# Falcon.net
KiCad netlist of a schematic drawn in Altium Designer
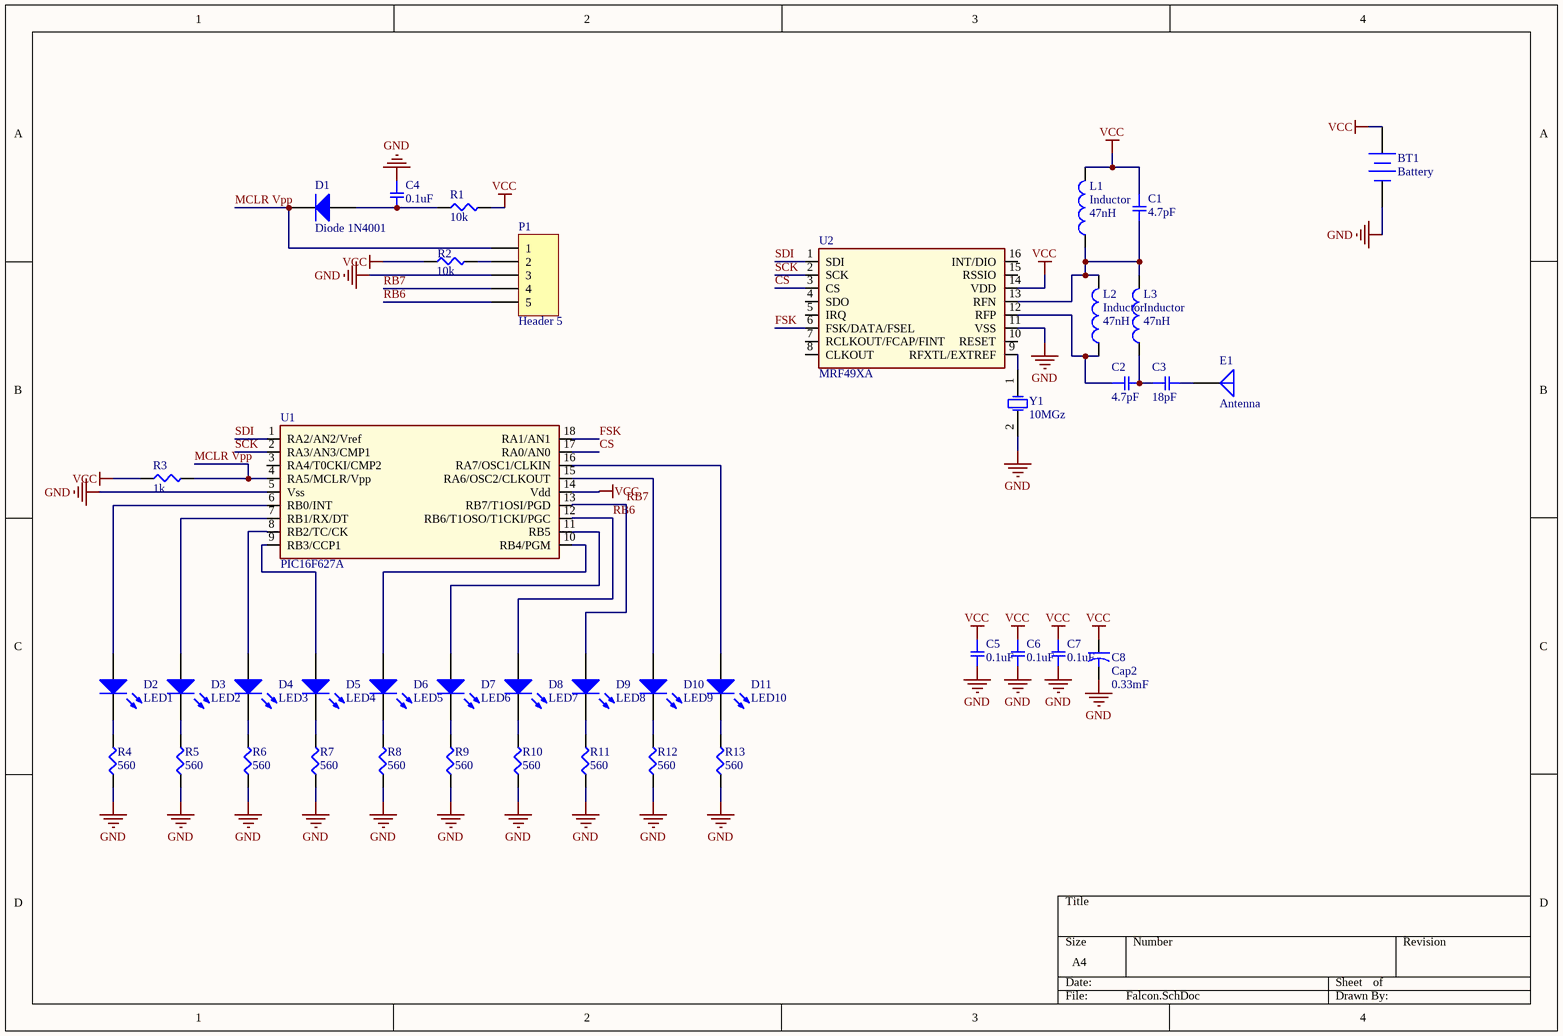
[diagram p0: Falcon.SchDoc]

(export (version "E")
  (design (tool "Eeschema 10.0.6"))
  (components
    (comp (ref "BT1")
      (value "Battery")
      (footprint "BAT-2")
      (description "Multicell Battery")
      (fields (field (name "PUBLISHER") "Altium Limited"))
      (libsource (lib "Miscellaneous Devices") (part "Battery"))
    )
    (comp (ref "C1")
      (value "4.7pF")
      (footprint "SMD-1206C")
      (description "CAP CER 0.033UF 250V X7T 1206")
      (fields
        (field (name "DIGI-KEY PART NUMBER") "490-13989-1-ND")
        (field (name "PART NUMBER") "GC331AD72E333KX01D")
      )
      (libsource (lib "capacitor_murata_1206") (part "GC331AD72E333KX01D"))
    )
    (comp (ref "C2")
      (value "4.7pF")
      (footprint "SMD-1206C")
      (description "CAP CER 0.033UF 250V X7T 1206")
      (fields
        (field (name "DIGI-KEY PART NUMBER") "490-13989-1-ND")
        (field (name "PART NUMBER") "GC331AD72E333KX01D")
      )
      (libsource (lib "capacitor_murata_1206") (part "GC331AD72E333KX01D"))
    )
    (comp (ref "C3")
      (value "18pF")
      (footprint "SMD-1206C")
      (description "CAP CER 0.033UF 250V X7T 1206")
      (fields
        (field (name "DIGI-KEY PART NUMBER") "490-13989-1-ND")
        (field (name "PART NUMBER") "GC331AD72E333KX01D")
      )
      (libsource (lib "capacitor_murata_1206") (part "GC331AD72E333KX01D"))
    )
    (comp (ref "C4")
      (value "0.1uF")
      (footprint "SMD-0805C")
      (description "CAP CER 10000PF 250V X7T 0805")
      (fields
        (field (name "DIGI-KEY PART NUMBER") "490-13986-1-ND")
        (field (name "PART NUMBER") "GC321AD72E103KX01D")
      )
      (libsource (lib "capacitor_murata_0805") (part "GC321AD72E103KX01D"))
    )
    (comp (ref "C5")
      (value "0.1uF")
      (footprint "SMD-0805C")
      (description "CAP CER 10000PF 250V X7T 0805")
      (fields
        (field (name "DIGI-KEY PART NUMBER") "490-13986-1-ND")
        (field (name "PART NUMBER") "GC321AD72E103KX01D")
      )
      (libsource (lib "capacitor_murata_0805") (part "GC321AD72E103KX01D"))
    )
    (comp (ref "C6")
      (value "0.1uF")
      (footprint "SMD-0805C")
      (description "CAP CER 10000PF 250V X7T 0805")
      (fields
        (field (name "DIGI-KEY PART NUMBER") "490-13986-1-ND")
        (field (name "PART NUMBER") "GC321AD72E103KX01D")
      )
      (libsource (lib "capacitor_murata_0805") (part "GC321AD72E103KX01D"))
    )
    (comp (ref "C7")
      (value "0.1uF")
      (footprint "SMD-0805C")
      (description "CAP CER 10000PF 250V X7T 0805")
      (fields
        (field (name "DIGI-KEY PART NUMBER") "490-13986-1-ND")
        (field (name "PART NUMBER") "GC321AD72E103KX01D")
      )
      (libsource (lib "capacitor_murata_0805") (part "GC321AD72E103KX01D"))
    )
    (comp (ref "C8")
      (value "Cap2")
      (footprint "CAPR5-4X5")
      (description "Capacitor")
      (fields (field (name "ALTIUM_VALUE") "0.33mF") (field (name "PUBLISHER") "Altium Limited"))
      (libsource (lib "Miscellaneous Devices") (part "Cap2"))
    )
    (comp (ref "D1")
      (value "Diode 1N4001")
      (footprint "DO-41")
      (description "1 Amp General Purpose Rectifier")
      (fields (field (name "PUBLISHER") "Altium Limited"))
      (libsource (lib "Miscellaneous Devices") (part "Diode 1N4001"))
    )
    (comp (ref "D2")
      (value "LED1")
      (footprint "3.5X2.8X1.9")
      (description "Typical BLUE SiC LED")
      (fields (field (name "PUBLISHER") "Altium Limited"))
      (libsource (lib "Miscellaneous Devices") (part "LED3"))
    )
    (comp (ref "D3")
      (value "LED2")
      (footprint "3.5X2.8X1.9")
      (description "Typical BLUE SiC LED")
      (fields (field (name "PUBLISHER") "Altium Limited"))
      (libsource (lib "Miscellaneous Devices") (part "LED3"))
    )
    (comp (ref "D4")
      (value "LED3")
      (footprint "3.5X2.8X1.9")
      (description "Typical BLUE SiC LED")
      (fields (field (name "PUBLISHER") "Altium Limited"))
      (libsource (lib "Miscellaneous Devices") (part "LED3"))
    )
    (comp (ref "D5")
      (value "LED4")
      (footprint "3.5X2.8X1.9")
      (description "Typical BLUE SiC LED")
      (fields (field (name "PUBLISHER") "Altium Limited"))
      (libsource (lib "Miscellaneous Devices") (part "LED3"))
    )
    (comp (ref "D6")
      (value "LED5")
      (footprint "3.5X2.8X1.9")
      (description "Typical BLUE SiC LED")
      (fields (field (name "PUBLISHER") "Altium Limited"))
      (libsource (lib "Miscellaneous Devices") (part "LED3"))
    )
    (comp (ref "D7")
      (value "LED6")
      (footprint "3.5X2.8X1.9")
      (description "Typical BLUE SiC LED")
      (fields (field (name "PUBLISHER") "Altium Limited"))
      (libsource (lib "Miscellaneous Devices") (part "LED3"))
    )
    (comp (ref "D8")
      (value "LED7")
      (footprint "3.5X2.8X1.9")
      (description "Typical BLUE SiC LED")
      (fields (field (name "PUBLISHER") "Altium Limited"))
      (libsource (lib "Miscellaneous Devices") (part "LED3"))
    )
    (comp (ref "D9")
      (value "LED8")
      (footprint "3.5X2.8X1.9")
      (description "Typical BLUE SiC LED")
      (fields (field (name "PUBLISHER") "Altium Limited"))
      (libsource (lib "Miscellaneous Devices") (part "LED3"))
    )
    (comp (ref "D10")
      (value "LED9")
      (footprint "3.5X2.8X1.9")
      (description "Typical BLUE SiC LED")
      (fields (field (name "PUBLISHER") "Altium Limited"))
      (libsource (lib "Miscellaneous Devices") (part "LED3"))
    )
    (comp (ref "D11")
      (value "LED10")
      (footprint "3.5X2.8X1.9")
      (description "Typical BLUE SiC LED")
      (fields (field (name "PUBLISHER") "Altium Limited"))
      (libsource (lib "Miscellaneous Devices") (part "LED3"))
    )
    (comp (ref "E1")
      (value "Antenna")
      (footprint "PIN1")
      (description "Generic Antenna")
      (fields (field (name "PUBLISHER") "Altium Limited"))
      (libsource (lib "Miscellaneous Devices") (part "Antenna"))
    )
    (comp (ref "L1")
      (value "Inductor")
      (footprint "0402-A")
      (fields (field (name "ALTIUM_VALUE") "47nH") (field (name "PUBLISHER") "Altium Limited"))
      (libsource (lib "Miscellaneous Devices") (part "Inductor"))
    )
    (comp (ref "L2")
      (value "Inductor")
      (footprint "0402-A")
      (fields (field (name "ALTIUM_VALUE") "47nH") (field (name "PUBLISHER") "Altium Limited"))
      (libsource (lib "Miscellaneous Devices") (part "Inductor"))
    )
    (comp (ref "L3")
      (value "Inductor")
      (footprint "0402-A")
      (fields (field (name "ALTIUM_VALUE") "47nH") (field (name "PUBLISHER") "Altium Limited"))
      (libsource (lib "Miscellaneous Devices") (part "Inductor"))
    )
    (comp (ref "P1")
      (value "Header 5")
      (footprint "HDR1X5")
      (description "Header, 5-Pin")
      (fields (field (name "PUBLISHER") "Altium Limited"))
      (libsource (lib "Miscellaneous Connectors") (part "Header 5"))
    )
    (comp (ref "R1")
      (value "10k")
      (footprint "SMD-0805-RES")
      (description "RES SMD 1 OHM 1% 1/3W 0805")
      (fields (field (name "PART NUMBER") "ERJ-6BQF1R0V") (field (name "DIGI-KEY PART NUMBER") "P17499CT-ND"))
      (libsource (lib "Panasonic_ERJ_0805") (part "ERJ-6BQF1R0V"))
    )
    (comp (ref "R2")
      (value "10k")
      (footprint "SMD-0805-RES")
      (description "RES SMD 1 OHM 1% 1/3W 0805")
      (fields (field (name "PART NUMBER") "ERJ-6BQF1R0V") (field (name "DIGI-KEY PART NUMBER") "P17499CT-ND"))
      (libsource (lib "Panasonic_ERJ_0805") (part "ERJ-6BQF1R0V"))
    )
    (comp (ref "R3")
      (value "1k")
      (footprint "SMD-0805-RES")
      (description "RES SMD 1 OHM 1% 1/3W 0805")
      (fields (field (name "PART NUMBER") "ERJ-6BQF1R0V") (field (name "DIGI-KEY PART NUMBER") "P17499CT-ND"))
      (libsource (lib "Panasonic_ERJ_0805") (part "ERJ-6BQF1R0V"))
    )
    (comp (ref "R4")
      (value "560")
      (footprint "SMD-0805-RES")
      (description "RES SMD 1 OHM 1% 1/3W 0805")
      (fields (field (name "PART NUMBER") "ERJ-6BQF1R0V") (field (name "DIGI-KEY PART NUMBER") "P17499CT-ND"))
      (libsource (lib "Panasonic_ERJ_0805") (part "ERJ-6BQF1R0V"))
    )
    (comp (ref "R5")
      (value "560")
      (footprint "SMD-0805-RES")
      (description "RES SMD 1 OHM 1% 1/3W 0805")
      (fields (field (name "PART NUMBER") "ERJ-6BQF1R0V") (field (name "DIGI-KEY PART NUMBER") "P17499CT-ND"))
      (libsource (lib "Panasonic_ERJ_0805") (part "ERJ-6BQF1R0V"))
    )
    (comp (ref "R6")
      (value "560")
      (footprint "SMD-0805-RES")
      (description "RES SMD 1 OHM 1% 1/3W 0805")
      (fields (field (name "PART NUMBER") "ERJ-6BQF1R0V") (field (name "DIGI-KEY PART NUMBER") "P17499CT-ND"))
      (libsource (lib "Panasonic_ERJ_0805") (part "ERJ-6BQF1R0V"))
    )
    (comp (ref "R7")
      (value "560")
      (footprint "SMD-0805-RES")
      (description "RES SMD 1 OHM 1% 1/3W 0805")
      (fields (field (name "PART NUMBER") "ERJ-6BQF1R0V") (field (name "DIGI-KEY PART NUMBER") "P17499CT-ND"))
      (libsource (lib "Panasonic_ERJ_0805") (part "ERJ-6BQF1R0V"))
    )
    (comp (ref "R8")
      (value "560")
      (footprint "SMD-0805-RES")
      (description "RES SMD 1 OHM 1% 1/3W 0805")
      (fields (field (name "PART NUMBER") "ERJ-6BQF1R0V") (field (name "DIGI-KEY PART NUMBER") "P17499CT-ND"))
      (libsource (lib "Panasonic_ERJ_0805") (part "ERJ-6BQF1R0V"))
    )
    (comp (ref "R9")
      (value "560")
      (footprint "SMD-0805-RES")
      (description "RES SMD 1 OHM 1% 1/3W 0805")
      (fields (field (name "PART NUMBER") "ERJ-6BQF1R0V") (field (name "DIGI-KEY PART NUMBER") "P17499CT-ND"))
      (libsource (lib "Panasonic_ERJ_0805") (part "ERJ-6BQF1R0V"))
    )
    (comp (ref "R10")
      (value "560")
      (footprint "SMD-0805-RES")
      (description "RES SMD 1 OHM 1% 1/3W 0805")
      (fields (field (name "PART NUMBER") "ERJ-6BQF1R0V") (field (name "DIGI-KEY PART NUMBER") "P17499CT-ND"))
      (libsource (lib "Panasonic_ERJ_0805") (part "ERJ-6BQF1R0V"))
    )
    (comp (ref "R11")
      (value "560")
      (footprint "SMD-0805-RES")
      (description "RES SMD 1 OHM 1% 1/3W 0805")
      (fields (field (name "PART NUMBER") "ERJ-6BQF1R0V") (field (name "DIGI-KEY PART NUMBER") "P17499CT-ND"))
      (libsource (lib "Panasonic_ERJ_0805") (part "ERJ-6BQF1R0V"))
    )
    (comp (ref "R12")
      (value "560")
      (footprint "SMD-0805-RES")
      (description "RES SMD 1 OHM 1% 1/3W 0805")
      (fields (field (name "PART NUMBER") "ERJ-6BQF1R0V") (field (name "DIGI-KEY PART NUMBER") "P17499CT-ND"))
      (libsource (lib "Panasonic_ERJ_0805") (part "ERJ-6BQF1R0V"))
    )
    (comp (ref "R13")
      (value "560")
      (footprint "SMD-0805-RES")
      (description "RES SMD 1 OHM 1% 1/3W 0805")
      (fields (field (name "PART NUMBER") "ERJ-6BQF1R0V") (field (name "DIGI-KEY PART NUMBER") "P17499CT-ND"))
      (libsource (lib "Panasonic_ERJ_0805") (part "ERJ-6BQF1R0V"))
    )
    (comp (ref "U1")
      (value "PIC16F627A")
      (footprint "RCU:PIC16F627A")
      (libsource (lib "RCU") (part "PIC16F627A"))
    )
    (comp (ref "U2") (value "MRF49XA") (footprint "RCU:MRF49XA") (libsource (lib "RCU") (part "MRF49XA")))
    (comp (ref "Y1")
      (value "10MGz")
      (footprint "R38")
      (description "Crystal Oscillator")
      (fields (field (name "PUBLISHER") "Altium Limited"))
      (libsource (lib "Miscellaneous Devices") (part "XTAL"))
    )
  )
  (nets
    (net (code "1") (name "/CS") (class "Default")
      (node (ref "U1") (pin "17") (pinfunction "RA0/AN0_17") (pintype "passive"))
      (node (ref "U2") (pin "3") (pinfunction "CS_3") (pintype "passive"))
    )
    (net (code "2") (name "/FSK") (class "Default")
      (node (ref "U1") (pin "18") (pinfunction "RA1/AN1_18") (pintype "passive"))
      (node (ref "U2") (pin "6") (pinfunction "FSK/DATA/FSEL_6") (pintype "passive"))
    )
    (net (code "3") (name "/MCLR Vpp") (class "Default")
      (node (ref "D1") (pin "2") (pinfunction "K_2") (pintype "passive"))
      (node (ref "P1") (pin "1") (pinfunction "1_1") (pintype "passive"))
      (node (ref "R3") (pin "2") (pinfunction "2_2") (pintype "passive"))
      (node (ref "U1") (pin "4") (pinfunction "RA5/MCLR/Vpp_4") (pintype "passive"))
    )
    (net (code "4") (name "/RB6") (class "Default")
      (node (ref "D8") (pin "1") (pinfunction "A_1") (pintype "passive"))
      (node (ref "P1") (pin "5") (pinfunction "5_5") (pintype "passive"))
      (node (ref "U1") (pin "12") (pinfunction "RB6/T1OSO/T1CKI/PGC_12") (pintype "passive"))
    )
    (net (code "5") (name "/RB7") (class "Default")
      (node (ref "D9") (pin "1") (pinfunction "A_1") (pintype "passive"))
      (node (ref "P1") (pin "4") (pinfunction "4_4") (pintype "passive"))
      (node (ref "U1") (pin "13") (pinfunction "RB7/T1OSI/PGD_13") (pintype "passive"))
    )
    (net (code "6") (name "/SCK") (class "Default")
      (node (ref "U1") (pin "2") (pinfunction "RA3/AN3/CMP1_2") (pintype "passive"))
      (node (ref "U2") (pin "2") (pinfunction "SCK_2") (pintype "passive"))
    )
    (net (code "7") (name "/SDI") (class "Default")
      (node (ref "U1") (pin "1") (pinfunction "RA2/AN2/Vref_1") (pintype "passive"))
      (node (ref "U2") (pin "1") (pinfunction "SDI_1") (pintype "passive"))
    )
    (net (code "8") (name "GND") (class "Default")
      (node (ref "BT1") (pin "2") (pinfunction "-_2") (pintype "passive"))
      (node (ref "C4") (pin "1") (pinfunction "1_1") (pintype "passive"))
      (node (ref "C5") (pin "2") (pinfunction "2_2") (pintype "passive"))
      (node (ref "C6") (pin "2") (pinfunction "2_2") (pintype "passive"))
      (node (ref "C7") (pin "2") (pinfunction "2_2") (pintype "passive"))
      (node (ref "C8") (pin "2") (pinfunction "2_2") (pintype "passive"))
      (node (ref "P1") (pin "3") (pinfunction "3_3") (pintype "passive"))
      (node (ref "R10") (pin "1") (pinfunction "1_1") (pintype "passive"))
      (node (ref "R11") (pin "1") (pinfunction "1_1") (pintype "passive"))
      (node (ref "R12") (pin "1") (pinfunction "1_1") (pintype "passive"))
      (node (ref "R13") (pin "1") (pinfunction "1_1") (pintype "passive"))
      (node (ref "R4") (pin "1") (pinfunction "1_1") (pintype "passive"))
      (node (ref "R5") (pin "1") (pinfunction "1_1") (pintype "passive"))
      (node (ref "R6") (pin "1") (pinfunction "1_1") (pintype "passive"))
      (node (ref "R7") (pin "1") (pinfunction "1_1") (pintype "passive"))
      (node (ref "R8") (pin "1") (pinfunction "1_1") (pintype "passive"))
      (node (ref "R9") (pin "1") (pinfunction "1_1") (pintype "passive"))
      (node (ref "U1") (pin "5") (pinfunction "Vss_5") (pintype "passive"))
      (node (ref "U2") (pin "11") (pinfunction "VSS_11") (pintype "passive"))
      (node (ref "Y1") (pin "2") (pinfunction "OSC2_2") (pintype "passive"))
    )
    (net (code "9") (name "Net-(C2-Pad2)") (class "Default")
      (node (ref "C2") (pin "2") (pinfunction "2_2") (pintype "passive"))
      (node (ref "C3") (pin "1") (pinfunction "1_1") (pintype "passive"))
      (node (ref "L3") (pin "1") (pinfunction "1_1") (pintype "passive"))
    )
    (net (code "10") (name "Net-(D1-A)") (class "Default")
      (node (ref "C4") (pin "2") (pinfunction "2_2") (pintype "passive"))
      (node (ref "D1") (pin "1") (pinfunction "A_1") (pintype "passive"))
      (node (ref "R1") (pin "1") (pinfunction "1_1") (pintype "passive"))
    )
    (net (code "11") (name "Net-(D2-A)") (class "Default")
      (node (ref "D2") (pin "1") (pinfunction "A_1") (pintype "passive"))
      (node (ref "U1") (pin "6") (pinfunction "RB0/INT_6") (pintype "passive"))
    )
    (net (code "12") (name "Net-(D2-K)") (class "Default")
      (node (ref "D2") (pin "2") (pinfunction "K_2") (pintype "passive"))
      (node (ref "R4") (pin "2") (pinfunction "2_2") (pintype "passive"))
    )
    (net (code "13") (name "Net-(D3-A)") (class "Default")
      (node (ref "D3") (pin "1") (pinfunction "A_1") (pintype "passive"))
      (node (ref "U1") (pin "7") (pinfunction "RB1/RX/DT_7") (pintype "passive"))
    )
    (net (code "14") (name "Net-(D3-K)") (class "Default")
      (node (ref "D3") (pin "2") (pinfunction "K_2") (pintype "passive"))
      (node (ref "R5") (pin "2") (pinfunction "2_2") (pintype "passive"))
    )
    (net (code "15") (name "Net-(D4-A)") (class "Default")
      (node (ref "D4") (pin "1") (pinfunction "A_1") (pintype "passive"))
      (node (ref "U1") (pin "8") (pinfunction "RB2/TC/CK_8") (pintype "passive"))
    )
    (net (code "16") (name "Net-(D4-K)") (class "Default")
      (node (ref "D4") (pin "2") (pinfunction "K_2") (pintype "passive"))
      (node (ref "R6") (pin "2") (pinfunction "2_2") (pintype "passive"))
    )
    (net (code "17") (name "Net-(D5-A)") (class "Default")
      (node (ref "D5") (pin "1") (pinfunction "A_1") (pintype "passive"))
      (node (ref "U1") (pin "9") (pinfunction "RB3/CCP1_9") (pintype "passive"))
    )
    (net (code "18") (name "Net-(D5-K)") (class "Default")
      (node (ref "D5") (pin "2") (pinfunction "K_2") (pintype "passive"))
      (node (ref "R7") (pin "2") (pinfunction "2_2") (pintype "passive"))
    )
    (net (code "19") (name "Net-(D6-A)") (class "Default")
      (node (ref "D6") (pin "1") (pinfunction "A_1") (pintype "passive"))
      (node (ref "U1") (pin "10") (pinfunction "RB4/PGM_10") (pintype "passive"))
    )
    (net (code "20") (name "Net-(D6-K)") (class "Default")
      (node (ref "D6") (pin "2") (pinfunction "K_2") (pintype "passive"))
      (node (ref "R8") (pin "2") (pinfunction "2_2") (pintype "passive"))
    )
    (net (code "21") (name "Net-(D7-A)") (class "Default")
      (node (ref "D7") (pin "1") (pinfunction "A_1") (pintype "passive"))
      (node (ref "U1") (pin "11") (pinfunction "RB5_11") (pintype "passive"))
    )
    (net (code "22") (name "Net-(D7-K)") (class "Default")
      (node (ref "D7") (pin "2") (pinfunction "K_2") (pintype "passive"))
      (node (ref "R9") (pin "2") (pinfunction "2_2") (pintype "passive"))
    )
    (net (code "23") (name "Net-(D8-K)") (class "Default")
      (node (ref "D8") (pin "2") (pinfunction "K_2") (pintype "passive"))
      (node (ref "R10") (pin "2") (pinfunction "2_2") (pintype "passive"))
    )
    (net (code "24") (name "Net-(D9-K)") (class "Default")
      (node (ref "D9") (pin "2") (pinfunction "K_2") (pintype "passive"))
      (node (ref "R11") (pin "2") (pinfunction "2_2") (pintype "passive"))
    )
    (net (code "25") (name "Net-(D10-A)") (class "Default")
      (node (ref "D10") (pin "1") (pinfunction "A_1") (pintype "passive"))
      (node (ref "U1") (pin "15") (pinfunction "RA6/OSC2/CLKOUT_15") (pintype "passive"))
    )
    (net (code "26") (name "Net-(D10-K)") (class "Default")
      (node (ref "D10") (pin "2") (pinfunction "K_2") (pintype "passive"))
      (node (ref "R12") (pin "2") (pinfunction "2_2") (pintype "passive"))
    )
    (net (code "27") (name "Net-(D11-A)") (class "Default")
      (node (ref "D11") (pin "1") (pinfunction "A_1") (pintype "passive"))
      (node (ref "U1") (pin "16") (pinfunction "RA7/OSC1/CLKIN_16") (pintype "passive"))
    )
    (net (code "28") (name "Net-(D11-K)") (class "Default")
      (node (ref "D11") (pin "2") (pinfunction "K_2") (pintype "passive"))
      (node (ref "R13") (pin "2") (pinfunction "2_2") (pintype "passive"))
    )
    (net (code "29") (name "Net-(E1-A)") (class "Default")
      (node (ref "C3") (pin "2") (pinfunction "2_2") (pintype "passive"))
      (node (ref "E1") (pin "1") (pinfunction "A_1") (pintype "passive"))
    )
    (net (code "30") (name "Net-(P1-Pad2)") (class "Default")
      (node (ref "P1") (pin "2") (pinfunction "2_2") (pintype "passive"))
      (node (ref "R2") (pin "2") (pinfunction "2_2") (pintype "passive"))
    )
    (net (code "31") (name "Net-(U2-RFN)") (class "Default")
      (node (ref "C1") (pin "2") (pinfunction "2_2") (pintype "passive"))
      (node (ref "L1") (pin "1") (pinfunction "1_1") (pintype "passive"))
      (node (ref "L2") (pin "2") (pinfunction "2_2") (pintype "passive"))
      (node (ref "L3") (pin "2") (pinfunction "2_2") (pintype "passive"))
      (node (ref "U2") (pin "13") (pinfunction "RFN_13") (pintype "passive"))
    )
    (net (code "32") (name "Net-(U2-RFP)") (class "Default")
      (node (ref "C2") (pin "1") (pinfunction "1_1") (pintype "passive"))
      (node (ref "L2") (pin "1") (pinfunction "1_1") (pintype "passive"))
      (node (ref "U2") (pin "12") (pinfunction "RFP_12") (pintype "passive"))
    )
    (net (code "33") (name "Net-(U2-RFXTL{slash}EXTREF)") (class "Default")
      (node (ref "U2") (pin "9") (pinfunction "RFXTL/EXTREF_9") (pintype "passive"))
      (node (ref "Y1") (pin "1") (pinfunction "OSC1_1") (pintype "passive"))
    )
    (net (code "34") (name "VCC") (class "Default")
      (node (ref "BT1") (pin "1") (pinfunction "+_1") (pintype "passive"))
      (node (ref "C1") (pin "1") (pinfunction "1_1") (pintype "passive"))
      (node (ref "C5") (pin "1") (pinfunction "1_1") (pintype "passive"))
      (node (ref "C6") (pin "1") (pinfunction "1_1") (pintype "passive"))
      (node (ref "C7") (pin "1") (pinfunction "1_1") (pintype "passive"))
      (node (ref "C8") (pin "1") (pinfunction "1_1") (pintype "passive"))
      (node (ref "L1") (pin "2") (pinfunction "2_2") (pintype "passive"))
      (node (ref "R1") (pin "2") (pinfunction "2_2") (pintype "passive"))
      (node (ref "R2") (pin "1") (pinfunction "1_1") (pintype "passive"))
      (node (ref "R3") (pin "1") (pinfunction "1_1") (pintype "passive"))
      (node (ref "U1") (pin "14") (pinfunction "Vdd_14") (pintype "passive"))
      (node (ref "U2") (pin "14") (pinfunction "VDD_14") (pintype "passive"))
    )
    (net (code "35") (name "unconnected-(U1-RA4{slash}T0CKI{slash}CMP2-Pad3)") (class "Default")
      (node (ref "U1") (pin "3") (pinfunction "RA4/T0CKI/CMP2_3") (pintype "passive"))
    )
    (net (code "36") (name "unconnected-(U2-CLKOUT-Pad8)") (class "Default")
      (node (ref "U2") (pin "8") (pinfunction "CLKOUT_8") (pintype "passive"))
    )
    (net (code "37") (name "unconnected-(U2-INT{slash}DIO-Pad16)") (class "Default")
      (node (ref "U2") (pin "16") (pinfunction "INT/DIO_16") (pintype "passive"))
    )
    (net (code "38") (name "unconnected-(U2-IRQ-Pad5)") (class "Default")
      (node (ref "U2") (pin "5") (pinfunction "IRQ_5") (pintype "passive"))
    )
    (net (code "39") (name "unconnected-(U2-RCLKOUT{slash}FCAP{slash}FINT-Pad7)") (class "Default")
      (node (ref "U2") (pin "7") (pinfunction "RCLKOUT/FCAP/FINT_7") (pintype "passive"))
    )
    (net (code "40") (name "unconnected-(U2-RESET-Pad10)") (class "Default")
      (node (ref "U2") (pin "10") (pinfunction "RESET_10") (pintype "passive"))
    )
    (net (code "41") (name "unconnected-(U2-RSSIO-Pad15)") (class "Default")
      (node (ref "U2") (pin "15") (pinfunction "RSSIO_15") (pintype "passive"))
    )
    (net (code "42") (name "unconnected-(U2-SDO-Pad4)") (class "Default")
      (node (ref "U2") (pin "4") (pinfunction "SDO_4") (pintype "passive"))
    )
  )
)
